# IRQF401RCT6.net
KiCad netlist of a schematic drawn in EAGLE
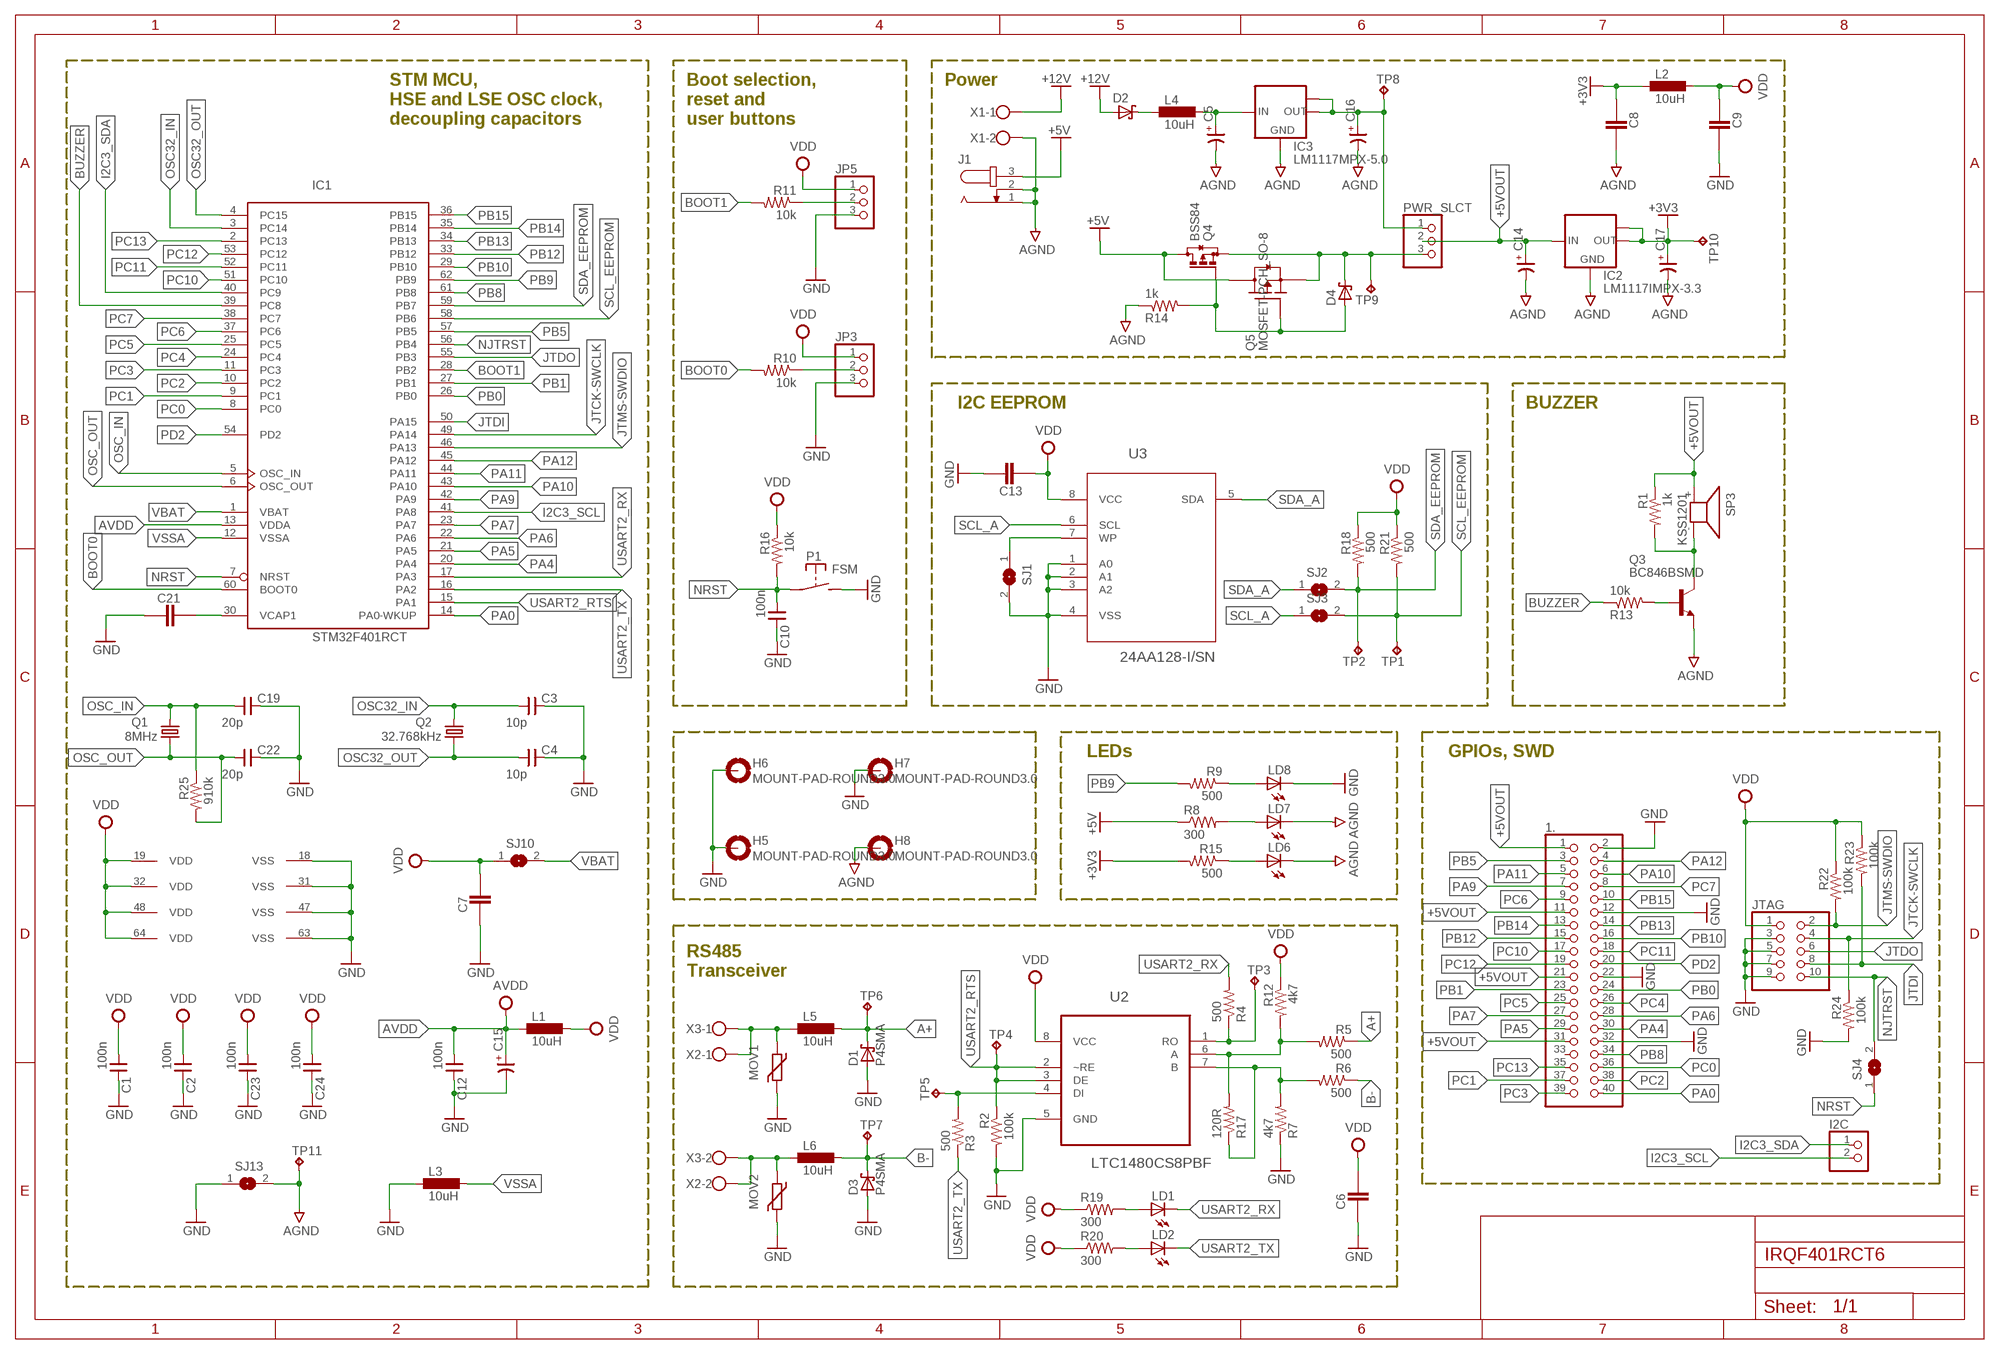
[diagram p0: schematic, sheet 1]

(export (version "E")
  (design (tool "Eeschema 10.0.6"))
  (components
    (comp (ref "1.")
      (value "PINHD-2X20")
      (footprint "eagle-import:2X20")
      (libsource (lib "eagle-import") (part "PINHD-2X20"))
    )
    (comp (ref "C1")
      (value "100n")
      (footprint "eagle-import:0805")
      (libsource (lib "eagle-import") (part "CNP-0805"))
    )
    (comp (ref "C2")
      (value "100n")
      (footprint "eagle-import:0805")
      (libsource (lib "eagle-import") (part "CNP-0805"))
    )
    (comp (ref "C3")
      (value "10p")
      (footprint "eagle-import:0805")
      (libsource (lib "eagle-import") (part "CNP-0805"))
    )
    (comp (ref "C4")
      (value "10p")
      (footprint "eagle-import:0805")
      (libsource (lib "eagle-import") (part "CNP-0805"))
    )
    (comp (ref "C5")
      (value "CP-3258-TE-B")
      (footprint "eagle-import:3528-TE-B")
      (libsource (lib "eagle-import") (part "CP-3258-TE-B"))
    )
    (comp (ref "C6")
      (value "CAPACITOR_1206")
      (footprint "eagle-import:CAPC3215X168N")
      (libsource (lib "eagle-import") (part "CAPACITOR_1206"))
    )
    (comp (ref "C7")
      (value "CAPACITOR_1206")
      (footprint "eagle-import:CAPC3215X168N")
      (libsource (lib "eagle-import") (part "CAPACITOR_1206"))
    )
    (comp (ref "C8")
      (value "CAPACITOR_1206")
      (footprint "eagle-import:CAPC3215X168N")
      (libsource (lib "eagle-import") (part "CAPACITOR_1206"))
    )
    (comp (ref "C9")
      (value "CAPACITOR_1206")
      (footprint "eagle-import:CAPC3215X168N")
      (libsource (lib "eagle-import") (part "CAPACITOR_1206"))
    )
    (comp (ref "C10")
      (value "100n")
      (footprint "eagle-import:0805")
      (libsource (lib "eagle-import") (part "CNP-0805"))
    )
    (comp (ref "C12")
      (value "100n")
      (footprint "eagle-import:0805")
      (libsource (lib "eagle-import") (part "CNP-0805"))
    )
    (comp (ref "C13")
      (value "CAPACITOR_1206")
      (footprint "eagle-import:CAPC3215X168N")
      (libsource (lib "eagle-import") (part "CAPACITOR_1206"))
    )
    (comp (ref "C14")
      (value "CP-3258-TE-B")
      (footprint "eagle-import:3528-TE-B")
      (libsource (lib "eagle-import") (part "CP-3258-TE-B"))
    )
    (comp (ref "C15")
      (value "CP-3216")
      (footprint "eagle-import:3216_T")
      (libsource (lib "eagle-import") (part "CP-3216"))
    )
    (comp (ref "C16")
      (value "CP-3216-TE-A")
      (footprint "eagle-import:3216-TE-A")
      (libsource (lib "eagle-import") (part "CP-3216-TE-A"))
    )
    (comp (ref "C17")
      (value "CP-3216-TE-A")
      (footprint "eagle-import:3216-TE-A")
      (libsource (lib "eagle-import") (part "CP-3216-TE-A"))
    )
    (comp (ref "C19")
      (value "20p")
      (footprint "eagle-import:0805")
      (libsource (lib "eagle-import") (part "CNP-0805"))
    )
    (comp (ref "C21")
      (value "CAPACITOR_1206")
      (footprint "eagle-import:CAPC3215X168N")
      (libsource (lib "eagle-import") (part "CAPACITOR_1206"))
    )
    (comp (ref "C22")
      (value "20p")
      (footprint "eagle-import:0805")
      (libsource (lib "eagle-import") (part "CNP-0805"))
    )
    (comp (ref "C23")
      (value "100n")
      (footprint "eagle-import:0805")
      (libsource (lib "eagle-import") (part "CNP-0805"))
    )
    (comp (ref "C24")
      (value "100n")
      (footprint "eagle-import:0805")
      (libsource (lib "eagle-import") (part "CNP-0805"))
    )
    (comp (ref "D1")
      (value "P4SMA")
      (footprint "eagle-import:SMB")
      (libsource (lib "eagle-import") (part "SCHOTTKY-DIODESMD"))
    )
    (comp (ref "D2")
      (value "SCHOTTKY_SMA")
      (footprint "eagle-import:DIOM5326X292N")
      (libsource (lib "eagle-import") (part "SCHOTTKY_SMA"))
    )
    (comp (ref "D3")
      (value "P4SMA")
      (footprint "eagle-import:SMB")
      (libsource (lib "eagle-import") (part "SCHOTTKY-DIODESMD"))
    )
    (comp (ref "D4")
      (value "SCHOTTKY_SMA")
      (footprint "eagle-import:DIOM5326X292N")
      (libsource (lib "eagle-import") (part "SCHOTTKY_SMA"))
    )
    (comp (ref "H5")
      (value "MOUNT-PAD-ROUND3.0")
      (footprint "eagle-import:3,0-PAD")
      (libsource (lib "eagle-import") (part "MOUNT-PAD-ROUND3.0"))
    )
    (comp (ref "H6")
      (value "MOUNT-PAD-ROUND3.0")
      (footprint "eagle-import:3,0-PAD")
      (libsource (lib "eagle-import") (part "MOUNT-PAD-ROUND3.0"))
    )
    (comp (ref "H7")
      (value "MOUNT-PAD-ROUND3.0")
      (footprint "eagle-import:3,0-PAD")
      (libsource (lib "eagle-import") (part "MOUNT-PAD-ROUND3.0"))
    )
    (comp (ref "H8")
      (value "MOUNT-PAD-ROUND3.0")
      (footprint "eagle-import:3,0-PAD")
      (libsource (lib "eagle-import") (part "MOUNT-PAD-ROUND3.0"))
    )
    (comp (ref "I2C")
      (value "PINHD-1X2")
      (footprint "eagle-import:1X02")
      (libsource (lib "eagle-import") (part "PINHD-1X2"))
    )
    (comp (ref "IC1")
      (value "STM32F401RCT")
      (footprint "eagle-import:LQFP64")
      (libsource (lib "eagle-import") (part "STM32F401RTC"))
    )
    (comp (ref "IC2")
      (value "LM1117IMPX-3.3")
      (footprint "eagle-import:SOT223")
      (libsource (lib "eagle-import") (part "LM1117IMPX-3.3"))
    )
    (comp (ref "IC3")
      (value "LM1117MPX-5.0")
      (footprint "eagle-import:SOT223")
      (libsource (lib "eagle-import") (part "LM1117MPX-5.0"))
    )
    (comp (ref "J1")
      (value "JACK-PLUG1")
      (footprint "eagle-import:SPC4078")
      (libsource (lib "eagle-import") (part "JACK-PLUG1"))
    )
    (comp (ref "JP3")
      (value "PINHD-1X3")
      (footprint "eagle-import:1X03")
      (libsource (lib "eagle-import") (part "PINHD-1X3"))
    )
    (comp (ref "JP5")
      (value "PINHD-1X3")
      (footprint "eagle-import:1X03")
      (libsource (lib "eagle-import") (part "PINHD-1X3"))
    )
    (comp (ref "JTAG")
      (value "PINHD-2X5")
      (footprint "eagle-import:2X05")
      (libsource (lib "eagle-import") (part "PINHD-2X5"))
    )
    (comp (ref "L1")
      (value "10uH")
      (footprint "eagle-import:INDC1608X95N")
      (libsource (lib "eagle-import") (part "INDUCTOR_0603"))
    )
    (comp (ref "L2")
      (value "10uH")
      (footprint "eagle-import:INDC1608X95N")
      (libsource (lib "eagle-import") (part "INDUCTOR_0603"))
    )
    (comp (ref "L3")
      (value "10uH")
      (footprint "eagle-import:INDC1608X95N")
      (libsource (lib "eagle-import") (part "INDUCTOR_0603"))
    )
    (comp (ref "L4")
      (value "10uH")
      (footprint "eagle-import:INDC1608X95N")
      (libsource (lib "eagle-import") (part "INDUCTOR_0603"))
    )
    (comp (ref "L5")
      (value "10uH")
      (footprint "eagle-import:INDC1608X95N")
      (libsource (lib "eagle-import") (part "INDUCTOR_0603"))
    )
    (comp (ref "L6")
      (value "10uH")
      (footprint "eagle-import:INDC1608X95N")
      (libsource (lib "eagle-import") (part "INDUCTOR_0603"))
    )
    (comp (ref "LD1")
      (value "LEDCHIPLED_0805")
      (footprint "eagle-import:CHIPLED_0805")
      (libsource (lib "eagle-import") (part "LEDCHIPLED_0805"))
    )
    (comp (ref "LD2")
      (value "LEDCHIPLED_0805")
      (footprint "eagle-import:CHIPLED_0805")
      (libsource (lib "eagle-import") (part "LEDCHIPLED_0805"))
    )
    (comp (ref "LD6")
      (value "LEDCHIPLED_0805")
      (footprint "eagle-import:CHIPLED_0805")
      (libsource (lib "eagle-import") (part "LEDCHIPLED_0805"))
    )
    (comp (ref "LD7")
      (value "LEDCHIPLED_0805")
      (footprint "eagle-import:CHIPLED_0805")
      (libsource (lib "eagle-import") (part "LEDCHIPLED_0805"))
    )
    (comp (ref "LD8")
      (value "LEDCHIPLED_0805")
      (footprint "eagle-import:CHIPLED_0805")
      (libsource (lib "eagle-import") (part "LEDCHIPLED_0805"))
    )
    (comp (ref "MOV1")
      (value "VARISTOR_0805")
      (footprint "eagle-import:VARC2012X70N")
      (libsource (lib "eagle-import") (part "VARISTOR_0805"))
    )
    (comp (ref "MOV2")
      (value "VARISTOR_0805")
      (footprint "eagle-import:VARC2012X70N")
      (libsource (lib "eagle-import") (part "VARISTOR_0805"))
    )
    (comp (ref "P1")
      (value "FSM")
      (footprint "eagle-import:FSM")
      (libsource (lib "eagle-import") (part "FSM"))
    )
    (comp (ref "PWR_SLCT")
      (value "PINHD-1X3")
      (footprint "eagle-import:1X03")
      (libsource (lib "eagle-import") (part "PINHD-1X3"))
    )
    (comp (ref "Q1")
      (value "8MHz")
      (footprint "eagle-import:HC49_S")
      (libsource (lib "eagle-import") (part "CRYTALHC49S"))
    )
    (comp (ref "Q2")
      (value "32.768kHz")
      (footprint "eagle-import:TC26H")
      (libsource (lib "eagle-import") (part "CRYTALTC26H"))
    )
    (comp (ref "Q3")
      (value "BC846BSMD")
      (footprint "eagle-import:SOT23")
      (libsource (lib "eagle-import") (part "BC846SMDB"))
    )
    (comp (ref "Q4")
      (value "BSS84")
      (footprint "eagle-import:SOT23")
      (libsource (lib "eagle-import") (part "BSS84"))
    )
    (comp (ref "Q5")
      (value "MOSFET-PCH_SO-8")
      (footprint "eagle-import:SOIC127P600X175-8AN")
      (libsource (lib "eagle-import") (part "MOSFET-PCH_SO-8"))
    )
    (comp (ref "R1")
      (value "1k")
      (footprint "eagle-import:M0805")
      (libsource (lib "eagle-import") (part "R-US_M0805"))
    )
    (comp (ref "R2")
      (value "100k")
      (footprint "eagle-import:M0805")
      (libsource (lib "eagle-import") (part "R-US_M0805"))
    )
    (comp (ref "R3")
      (value "500")
      (footprint "eagle-import:M0805")
      (libsource (lib "eagle-import") (part "R-US_M0805"))
    )
    (comp (ref "R4")
      (value "500")
      (footprint "eagle-import:M0805")
      (libsource (lib "eagle-import") (part "R-US_M0805"))
    )
    (comp (ref "R5")
      (value "500")
      (footprint "eagle-import:M0805")
      (libsource (lib "eagle-import") (part "R-US_M0805"))
    )
    (comp (ref "R6")
      (value "500")
      (footprint "eagle-import:M0805")
      (libsource (lib "eagle-import") (part "R-US_M0805"))
    )
    (comp (ref "R7")
      (value "4k7")
      (footprint "eagle-import:M0805")
      (libsource (lib "eagle-import") (part "R-US_M0805"))
    )
    (comp (ref "R8")
      (value "300")
      (footprint "eagle-import:M0805")
      (libsource (lib "eagle-import") (part "R-US_M0805"))
    )
    (comp (ref "R9")
      (value "500")
      (footprint "eagle-import:M0805")
      (libsource (lib "eagle-import") (part "R-US_M0805"))
    )
    (comp (ref "R10")
      (value "10k")
      (footprint "eagle-import:M0805")
      (libsource (lib "eagle-import") (part "R-US_M0805"))
    )
    (comp (ref "R11")
      (value "10k")
      (footprint "eagle-import:M0805")
      (libsource (lib "eagle-import") (part "R-US_M0805"))
    )
    (comp (ref "R12")
      (value "4k7")
      (footprint "eagle-import:M0805")
      (libsource (lib "eagle-import") (part "R-US_M0805"))
    )
    (comp (ref "R13")
      (value "10k")
      (footprint "eagle-import:M0805")
      (libsource (lib "eagle-import") (part "R-US_M0805"))
    )
    (comp (ref "R14")
      (value "1k")
      (footprint "eagle-import:M0805")
      (libsource (lib "eagle-import") (part "R-US_M0805"))
    )
    (comp (ref "R15")
      (value "500")
      (footprint "eagle-import:M0805")
      (libsource (lib "eagle-import") (part "R-US_M0805"))
    )
    (comp (ref "R16")
      (value "10k")
      (footprint "eagle-import:M0805")
      (libsource (lib "eagle-import") (part "R-US_M0805"))
    )
    (comp (ref "R17")
      (value "120R")
      (footprint "eagle-import:M0805")
      (libsource (lib "eagle-import") (part "R-US_M0805"))
    )
    (comp (ref "R18")
      (value "500")
      (footprint "eagle-import:M0805")
      (libsource (lib "eagle-import") (part "R-US_M0805"))
    )
    (comp (ref "R19")
      (value "300")
      (footprint "eagle-import:M0805")
      (libsource (lib "eagle-import") (part "R-US_M0805"))
    )
    (comp (ref "R20")
      (value "300")
      (footprint "eagle-import:M0805")
      (libsource (lib "eagle-import") (part "R-US_M0805"))
    )
    (comp (ref "R21")
      (value "500")
      (footprint "eagle-import:M0805")
      (libsource (lib "eagle-import") (part "R-US_M0805"))
    )
    (comp (ref "R22")
      (value "100k")
      (footprint "eagle-import:M0805")
      (libsource (lib "eagle-import") (part "R-US_M0805"))
    )
    (comp (ref "R23")
      (value "100k")
      (footprint "eagle-import:M0805")
      (libsource (lib "eagle-import") (part "R-US_M0805"))
    )
    (comp (ref "R24")
      (value "100k")
      (footprint "eagle-import:M0805")
      (libsource (lib "eagle-import") (part "R-US_M0805"))
    )
    (comp (ref "R25")
      (value "910k")
      (footprint "eagle-import:M0805")
      (libsource (lib "eagle-import") (part "R-US_M0805"))
    )
    (comp (ref "SJ1") (value "SJ") (footprint "eagle-import:SJ") (libsource (lib "eagle-import") (part "SJ")))
    (comp (ref "SJ2") (value "SJ") (footprint "eagle-import:SJ") (libsource (lib "eagle-import") (part "SJ")))
    (comp (ref "SJ3") (value "SJ") (footprint "eagle-import:SJ") (libsource (lib "eagle-import") (part "SJ")))
    (comp (ref "SJ4") (value "SJ") (footprint "eagle-import:SJ") (libsource (lib "eagle-import") (part "SJ")))
    (comp (ref "SJ10")
      (value "SJ")
      (footprint "eagle-import:SJ")
      (libsource (lib "eagle-import") (part "SJ"))
    )
    (comp (ref "SJ13")
      (value "SJ")
      (footprint "eagle-import:SJ")
      (libsource (lib "eagle-import") (part "SJ"))
    )
    (comp (ref "SP3")
      (value "KSS1201")
      (footprint "eagle-import:KSS1201")
      (libsource (lib "eagle-import") (part "KSS1201"))
    )
    (comp (ref "TP1")
      (value "TPTP10R")
      (footprint "eagle-import:TP10R")
      (libsource (lib "eagle-import") (part "TPTP10R"))
    )
    (comp (ref "TP2")
      (value "TPTP10R")
      (footprint "eagle-import:TP10R")
      (libsource (lib "eagle-import") (part "TPTP10R"))
    )
    (comp (ref "TP3")
      (value "TPTP10R")
      (footprint "eagle-import:TP10R")
      (libsource (lib "eagle-import") (part "TPTP10R"))
    )
    (comp (ref "TP4")
      (value "TPTP10R")
      (footprint "eagle-import:TP10R")
      (libsource (lib "eagle-import") (part "TPTP10R"))
    )
    (comp (ref "TP5")
      (value "TPTP10R")
      (footprint "eagle-import:TP10R")
      (libsource (lib "eagle-import") (part "TPTP10R"))
    )
    (comp (ref "TP6")
      (value "TPTP10R")
      (footprint "eagle-import:TP10R")
      (libsource (lib "eagle-import") (part "TPTP10R"))
    )
    (comp (ref "TP7")
      (value "TPTP10R")
      (footprint "eagle-import:TP10R")
      (libsource (lib "eagle-import") (part "TPTP10R"))
    )
    (comp (ref "TP8")
      (value "TPTP10R")
      (footprint "eagle-import:TP10R")
      (libsource (lib "eagle-import") (part "TPTP10R"))
    )
    (comp (ref "TP9")
      (value "TPTP10R")
      (footprint "eagle-import:TP10R")
      (libsource (lib "eagle-import") (part "TPTP10R"))
    )
    (comp (ref "TP10")
      (value "TPTP10R")
      (footprint "eagle-import:TP10R")
      (libsource (lib "eagle-import") (part "TPTP10R"))
    )
    (comp (ref "TP11")
      (value "TPTP10R")
      (footprint "eagle-import:TP10R")
      (libsource (lib "eagle-import") (part "TPTP10R"))
    )
    (comp (ref "U2")
      (value "LTC1480CS8PBF")
      (footprint "eagle-import:SOIC127P600X175-8N")
      (fields (field (name "MPN") "LTC1480CS8#PBF"))
      (libsource (lib "eagle-import") (part "LTC1480CS8PBF"))
    )
    (comp (ref "U3")
      (value "24AA128-I/SN")
      (footprint "eagle-import:SOIC127P600X175-8N")
      (libsource (lib "eagle-import") (part "24AA128-I/SN"))
    )
    (comp (ref "X1")
      (value "W237-102")
      (footprint "eagle-import:W237-102")
      (libsource (lib "eagle-import") (part "W237-102"))
    )
    (comp (ref "X2")
      (value "W237-102")
      (footprint "eagle-import:W237-102")
      (libsource (lib "eagle-import") (part "W237-102"))
    )
    (comp (ref "X3")
      (value "W237-102")
      (footprint "eagle-import:W237-102")
      (libsource (lib "eagle-import") (part "W237-102"))
    )
  )
  (nets
    (net (code "1") (name "+3V3") (class "Default")
      (node (ref "C17") (pin "+") (pinfunction "+_+") (pintype "passive"))
      (node (ref "C8") (pin "1") (pinfunction "1_1") (pintype "passive"))
      (node (ref "IC2") (pin "2") (pinfunction "OUT_2") (pintype "passive"))
      (node (ref "IC2") (pin "TAB") (pinfunction "OUT1_TAB") (pintype "passive"))
      (node (ref "L2") (pin "1") (pinfunction "1_1") (pintype "passive"))
      (node (ref "R15") (pin "2") (pinfunction "2_2") (pintype "passive"))
      (node (ref "TP10") (pin "TP") (pinfunction "TP_TP") (pintype "input"))
    )
    (net (code "2") (name "+5V") (class "Default")
      (node (ref "J1") (pin "3") (pinfunction "3_3") (pintype "passive"))
      (node (ref "Q4") (pin "3") (pinfunction "D_3") (pintype "passive"))
      (node (ref "Q5") (pin "5") (pinfunction "D_5") (pintype "passive"))
      (node (ref "R8") (pin "1") (pinfunction "1_1") (pintype "passive"))
    )
    (net (code "3") (name "+5VOUT") (class "Default")
      (node (ref "1.") (pin "1") (pinfunction "1_1") (pintype "passive"))
      (node (ref "1.") (pin "11") (pinfunction "11_11") (pintype "passive"))
      (node (ref "1.") (pin "21") (pinfunction "21_21") (pintype "passive"))
      (node (ref "1.") (pin "31") (pinfunction "31_31") (pintype "passive"))
      (node (ref "C14") (pin "+") (pinfunction "+_+") (pintype "passive"))
      (node (ref "IC2") (pin "3") (pinfunction "IN_3") (pintype "input"))
      (node (ref "PWR_SLCT") (pin "2") (pinfunction "2_2") (pintype "passive"))
      (node (ref "R1") (pin "1") (pinfunction "1_1") (pintype "passive"))
      (node (ref "SP3") (pin "+") (pinfunction "1_+") (pintype "passive"))
    )
    (net (code "4") (name "+12V") (class "Default")
      (node (ref "D2") (pin "A") (pinfunction "A_A") (pintype "passive"))
      (node (ref "X1") (pin "1") (pinfunction "KL_1") (pintype "passive"))
    )
    (net (code "5") (name "A+") (class "Default")
      (node (ref "D1") (pin "C") (pinfunction "C_C") (pintype "passive"))
      (node (ref "L5") (pin "2") (pinfunction "2_2") (pintype "passive"))
      (node (ref "R5") (pin "1") (pinfunction "1_1") (pintype "passive"))
      (node (ref "TP6") (pin "TP") (pinfunction "TP_TP") (pintype "input"))
    )
    (net (code "6") (name "AGND") (class "Default")
      (node (ref "C14") (pin "-") (pinfunction "-_-") (pintype "passive"))
      (node (ref "C16") (pin "-") (pinfunction "-_-") (pintype "passive"))
      (node (ref "C17") (pin "-") (pinfunction "-_-") (pintype "passive"))
      (node (ref "C5") (pin "-") (pinfunction "-_-") (pintype "passive"))
      (node (ref "C8") (pin "2") (pinfunction "2_2") (pintype "passive"))
      (node (ref "H8") (pin "B3,0") (pinfunction "MOUNT_B3,0") (pintype "passive"))
      (node (ref "IC2") (pin "1") (pinfunction "GND_1") (pintype "input"))
      (node (ref "IC3") (pin "1") (pinfunction "GND_1") (pintype "input"))
      (node (ref "J1") (pin "1") (pinfunction "1_1") (pintype "passive"))
      (node (ref "J1") (pin "2") (pinfunction "2_2") (pintype "passive"))
      (node (ref "LD6") (pin "C") (pinfunction "C_C") (pintype "passive"))
      (node (ref "LD7") (pin "C") (pinfunction "C_C") (pintype "passive"))
      (node (ref "Q3") (pin "2") (pinfunction "E_2") (pintype "passive"))
      (node (ref "R14") (pin "1") (pinfunction "1_1") (pintype "passive"))
      (node (ref "SJ13") (pin "2") (pinfunction "2_2") (pintype "passive"))
      (node (ref "TP11") (pin "TP") (pinfunction "TP_TP") (pintype "input"))
      (node (ref "X1") (pin "2") (pinfunction "KL_2") (pintype "passive"))
    )
    (net (code "7") (name "AVDD") (class "Default")
      (node (ref "C12") (pin "1") (pinfunction "1_1") (pintype "passive"))
      (node (ref "C15") (pin "+") (pinfunction "+_+") (pintype "passive"))
      (node (ref "IC1") (pin "13") (pinfunction "VDDA_13") (pintype "power_in"))
      (node (ref "L1") (pin "1") (pinfunction "1_1") (pintype "passive"))
    )
    (net (code "8") (name "B-") (class "Default")
      (node (ref "D3") (pin "C") (pinfunction "C_C") (pintype "passive"))
      (node (ref "L6") (pin "2") (pinfunction "2_2") (pintype "passive"))
      (node (ref "R6") (pin "1") (pinfunction "1_1") (pintype "passive"))
      (node (ref "TP7") (pin "TP") (pinfunction "TP_TP") (pintype "input"))
    )
    (net (code "9") (name "BOOT0") (class "Default")
      (node (ref "IC1") (pin "60") (pinfunction "BOOT0_60") (pintype "input"))
      (node (ref "R10") (pin "2") (pinfunction "2_2") (pintype "passive"))
    )
    (net (code "10") (name "BOOT1") (class "Default")
      (node (ref "IC1") (pin "28") (pinfunction "PB2_28") (pintype "bidirectional"))
      (node (ref "R11") (pin "2") (pinfunction "2_2") (pintype "passive"))
    )
    (net (code "11") (name "BUZZER") (class "Default")
      (node (ref "IC1") (pin "39") (pinfunction "PC8_39") (pintype "bidirectional"))
      (node (ref "R13") (pin "1") (pinfunction "1_1") (pintype "passive"))
    )
    (net (code "12") (name "GND") (class "Default")
      (node (ref "1.") (pin "12") (pinfunction "12_12") (pintype "passive"))
      (node (ref "1.") (pin "2") (pinfunction "2_2") (pintype "passive"))
      (node (ref "1.") (pin "22") (pinfunction "22_22") (pintype "passive"))
      (node (ref "1.") (pin "32") (pinfunction "32_32") (pintype "passive"))
      (node (ref "C1") (pin "2") (pinfunction "2_2") (pintype "passive"))
      (node (ref "C10") (pin "2") (pinfunction "2_2") (pintype "passive"))
      (node (ref "C12") (pin "2") (pinfunction "2_2") (pintype "passive"))
      (node (ref "C13") (pin "2") (pinfunction "2_2") (pintype "passive"))
      (node (ref "C15") (pin "-") (pinfunction "-_-") (pintype "passive"))
      (node (ref "C19") (pin "2") (pinfunction "2_2") (pintype "passive"))
      (node (ref "C2") (pin "2") (pinfunction "2_2") (pintype "passive"))
      (node (ref "C21") (pin "1") (pinfunction "1_1") (pintype "passive"))
      (node (ref "C22") (pin "2") (pinfunction "2_2") (pintype "passive"))
      (node (ref "C23") (pin "2") (pinfunction "2_2") (pintype "passive"))
      (node (ref "C24") (pin "2") (pinfunction "2_2") (pintype "passive"))
      (node (ref "C3") (pin "2") (pinfunction "2_2") (pintype "passive"))
      (node (ref "C4") (pin "2") (pinfunction "2_2") (pintype "passive"))
      (node (ref "C6") (pin "1") (pinfunction "1_1") (pintype "passive"))
      (node (ref "C7") (pin "1") (pinfunction "1_1") (pintype "passive"))
      (node (ref "C9") (pin "2") (pinfunction "2_2") (pintype "passive"))
      (node (ref "D1") (pin "A") (pinfunction "A_A") (pintype "passive"))
      (node (ref "D3") (pin "A") (pinfunction "A_A") (pintype "passive"))
      (node (ref "H5") (pin "B3,0") (pinfunction "MOUNT_B3,0") (pintype "passive"))
      (node (ref "H6") (pin "B3,0") (pinfunction "MOUNT_B3,0") (pintype "passive"))
      (node (ref "H7") (pin "B3,0") (pinfunction "MOUNT_B3,0") (pintype "passive"))
      (node (ref "IC1") (pin "18") (pinfunction "VSS_18") (pintype "power_in"))
      (node (ref "IC1") (pin "31") (pinfunction "VSS_31") (pintype "power_in"))
      (node (ref "IC1") (pin "47") (pinfunction "VSS_47") (pintype "power_in"))
      (node (ref "IC1") (pin "63") (pinfunction "VSS_63") (pintype "power_in"))
      (node (ref "JP3") (pin "3") (pinfunction "3_3") (pintype "passive"))
      (node (ref "JP5") (pin "3") (pinfunction "3_3") (pintype "passive"))
      (node (ref "JTAG") (pin "3") (pinfunction "3_3") (pintype "passive"))
      (node (ref "JTAG") (pin "5") (pinfunction "5_5") (pintype "passive"))
      (node (ref "JTAG") (pin "7") (pinfunction "7_7") (pintype "passive"))
      (node (ref "JTAG") (pin "9") (pinfunction "9_9") (pintype "passive"))
      (node (ref "L3") (pin "1") (pinfunction "1_1") (pintype "passive"))
      (node (ref "LD8") (pin "C") (pinfunction "C_C") (pintype "passive"))
      (node (ref "MOV1") (pin "1") (pinfunction "1_1") (pintype "passive"))
      (node (ref "MOV2") (pin "1") (pinfunction "1_1") (pintype "passive"))
      (node (ref "P1") (pin "P$2") (pinfunction "S_P$2") (pintype "passive"))
      (node (ref "R2") (pin "2") (pinfunction "2_2") (pintype "passive"))
      (node (ref "R24") (pin "2") (pinfunction "2_2") (pintype "passive"))
      (node (ref "R7") (pin "1") (pinfunction "1_1") (pintype "passive"))
      (node (ref "SJ1") (pin "2") (pinfunction "2_2") (pintype "passive"))
      (node (ref "SJ13") (pin "1") (pinfunction "1_1") (pintype "passive"))
      (node (ref "U2") (pin "5") (pinfunction "GND_5") (pintype "passive"))
      (node (ref "U3") (pin "1") (pinfunction "A0_1") (pintype "input"))
      (node (ref "U3") (pin "2") (pinfunction "A1_2") (pintype "input"))
      (node (ref "U3") (pin "3") (pinfunction "A2_3") (pintype "input"))
      (node (ref "U3") (pin "4") (pinfunction "VSS_4") (pintype "power_in"))
    )
    (net (code "13") (name "I2C3_SCL") (class "Default")
      (node (ref "I2C") (pin "2") (pinfunction "2_2") (pintype "passive"))
      (node (ref "IC1") (pin "41") (pinfunction "PA8_41") (pintype "bidirectional"))
    )
    (net (code "14") (name "I2C3_SDA") (class "Default")
      (node (ref "I2C") (pin "1") (pinfunction "1_1") (pintype "passive"))
      (node (ref "IC1") (pin "40") (pinfunction "PC9_40") (pintype "bidirectional"))
    )
    (net (code "15") (name "JTCK-SWCLK") (class "Default")
      (node (ref "IC1") (pin "49") (pinfunction "PA14_49") (pintype "bidirectional"))
      (node (ref "JTAG") (pin "4") (pinfunction "4_4") (pintype "passive"))
      (node (ref "R24") (pin "1") (pinfunction "1_1") (pintype "passive"))
    )
    (net (code "16") (name "JTDI") (class "Default")
      (node (ref "IC1") (pin "50") (pinfunction "PA15_50") (pintype "bidirectional"))
      (node (ref "JTAG") (pin "8") (pinfunction "8_8") (pintype "passive"))
      (node (ref "R23") (pin "2") (pinfunction "2_2") (pintype "passive"))
    )
    (net (code "17") (name "JTDO") (class "Default")
      (node (ref "IC1") (pin "55") (pinfunction "PB3_55") (pintype "bidirectional"))
      (node (ref "JTAG") (pin "6") (pinfunction "6_6") (pintype "passive"))
    )
    (net (code "18") (name "JTMS-SWDIO") (class "Default")
      (node (ref "IC1") (pin "46") (pinfunction "PA13_46") (pintype "bidirectional"))
      (node (ref "JTAG") (pin "2") (pinfunction "2_2") (pintype "passive"))
      (node (ref "R22") (pin "2") (pinfunction "2_2") (pintype "passive"))
    )
    (net (code "19") (name "NJTRST") (class "Default")
      (node (ref "IC1") (pin "56") (pinfunction "PB4_56") (pintype "bidirectional"))
      (node (ref "JTAG") (pin "10") (pinfunction "10_10") (pintype "passive"))
      (node (ref "SJ4") (pin "2") (pinfunction "2_2") (pintype "passive"))
    )
    (net (code "20") (name "NRST") (class "Default")
      (node (ref "C10") (pin "1") (pinfunction "1_1") (pintype "passive"))
      (node (ref "IC1") (pin "7") (pinfunction "NRST_7") (pintype "bidirectional"))
      (node (ref "P1") (pin "P$1") (pinfunction "P_P$1") (pintype "passive"))
      (node (ref "R16") (pin "2") (pinfunction "2_2") (pintype "passive"))
      (node (ref "SJ4") (pin "1") (pinfunction "1_1") (pintype "passive"))
    )
    (net (code "21") (name "Net-(D2-PadK)") (class "Default")
      (node (ref "D2") (pin "K") (pinfunction "K_K") (pintype "passive"))
      (node (ref "L4") (pin "1") (pinfunction "1_1") (pintype "passive"))
    )
    (net (code "22") (name "Net-(IC1A-VCAP1)") (class "Default")
      (node (ref "C21") (pin "2") (pinfunction "2_2") (pintype "passive"))
      (node (ref "IC1") (pin "30") (pinfunction "VCAP1_30") (pintype "power_in"))
    )
    (net (code "23") (name "Net-(IC3-IN)") (class "Default")
      (node (ref "C5") (pin "+") (pinfunction "+_+") (pintype "passive"))
      (node (ref "IC3") (pin "3") (pinfunction "IN_3") (pintype "input"))
      (node (ref "L4") (pin "2") (pinfunction "2_2") (pintype "passive"))
    )
    (net (code "24") (name "Net-(IC3-OUT)") (class "Default")
      (node (ref "C16") (pin "+") (pinfunction "+_+") (pintype "passive"))
      (node (ref "IC3") (pin "2") (pinfunction "OUT_2") (pintype "passive"))
      (node (ref "IC3") (pin "TAB") (pinfunction "OUT1_TAB") (pintype "passive"))
      (node (ref "PWR_SLCT") (pin "1") (pinfunction "1_1") (pintype "passive"))
      (node (ref "TP8") (pin "TP") (pinfunction "TP_TP") (pintype "input"))
    )
    (net (code "25") (name "Net-(JP3-Pad2)") (class "Default")
      (node (ref "JP3") (pin "2") (pinfunction "2_2") (pintype "passive"))
      (node (ref "R10") (pin "1") (pinfunction "1_1") (pintype "passive"))
    )
    (net (code "26") (name "Net-(JP5-Pad2)") (class "Default")
      (node (ref "JP5") (pin "2") (pinfunction "2_2") (pintype "passive"))
      (node (ref "R11") (pin "1") (pinfunction "1_1") (pintype "passive"))
    )
    (net (code "27") (name "Net-(LD1-PadA)") (class "Default")
      (node (ref "LD1") (pin "A") (pinfunction "A_A") (pintype "passive"))
      (node (ref "R19") (pin "2") (pinfunction "2_2") (pintype "passive"))
    )
    (net (code "28") (name "Net-(LD2-PadA)") (class "Default")
      (node (ref "LD2") (pin "A") (pinfunction "A_A") (pintype "passive"))
      (node (ref "R20") (pin "2") (pinfunction "2_2") (pintype "passive"))
    )
    (net (code "29") (name "Net-(LD6-PadA)") (class "Default")
      (node (ref "LD6") (pin "A") (pinfunction "A_A") (pintype "passive"))
      (node (ref "R15") (pin "1") (pinfunction "1_1") (pintype "passive"))
    )
    (net (code "30") (name "Net-(LD7-PadA)") (class "Default")
      (node (ref "LD7") (pin "A") (pinfunction "A_A") (pintype "passive"))
      (node (ref "R8") (pin "2") (pinfunction "2_2") (pintype "passive"))
    )
    (net (code "31") (name "Net-(LD8-PadA)") (class "Default")
      (node (ref "LD8") (pin "A") (pinfunction "A_A") (pintype "passive"))
      (node (ref "R9") (pin "1") (pinfunction "1_1") (pintype "passive"))
    )
    (net (code "32") (name "Net-(Q3-B)") (class "Default")
      (node (ref "Q3") (pin "1") (pinfunction "B_1") (pintype "passive"))
      (node (ref "R13") (pin "2") (pinfunction "2_2") (pintype "passive"))
    )
    (net (code "33") (name "Net-(Q3-C)") (class "Default")
      (node (ref "Q3") (pin "3") (pinfunction "C_3") (pintype "passive"))
      (node (ref "R1") (pin "2") (pinfunction "2_2") (pintype "passive"))
      (node (ref "SP3") (pin "-") (pinfunction "2_-") (pintype "passive"))
    )
    (net (code "34") (name "Net-(Q4-G)") (class "Default")
      (node (ref "D4") (pin "A") (pinfunction "A_A") (pintype "passive"))
      (node (ref "Q4") (pin "1") (pinfunction "G_1") (pintype "passive"))
      (node (ref "Q5") (pin "4") (pinfunction "G_4") (pintype "passive"))
      (node (ref "R14") (pin "2") (pinfunction "2_2") (pintype "passive"))
    )
    (net (code "35") (name "Net-(Q4-S)") (class "Default")
      (node (ref "D4") (pin "K") (pinfunction "K_K") (pintype "passive"))
      (node (ref "PWR_SLCT") (pin "3") (pinfunction "3_3") (pintype "passive"))
      (node (ref "Q4") (pin "2") (pinfunction "S_2") (pintype "passive"))
      (node (ref "Q5") (pin "1") (pinfunction "S_1") (pintype "passive"))
      (node (ref "TP9") (pin "TP") (pinfunction "TP_TP") (pintype "input"))
    )
    (net (code "36") (name "Net-(U2-A)") (class "Default")
      (node (ref "R12") (pin "2") (pinfunction "2_2") (pintype "passive"))
      (node (ref "R17") (pin "2") (pinfunction "2_2") (pintype "passive"))
      (node (ref "R5") (pin "2") (pinfunction "2_2") (pintype "passive"))
      (node (ref "U2") (pin "6") (pinfunction "A_6") (pintype "bidirectional"))
    )
    (net (code "37") (name "Net-(U2-B)") (class "Default")
      (node (ref "R17") (pin "1") (pinfunction "1_1") (pintype "passive"))
      (node (ref "R6") (pin "2") (pinfunction "2_2") (pintype "passive"))
      (node (ref "R7") (pin "2") (pinfunction "2_2") (pintype "passive"))
      (node (ref "U2") (pin "7") (pinfunction "B_7") (pintype "bidirectional"))
    )
    (net (code "38") (name "Net-(U2-DI)") (class "Default")
      (node (ref "R3") (pin "2") (pinfunction "2_2") (pintype "passive"))
      (node (ref "TP5") (pin "TP") (pinfunction "TP_TP") (pintype "input"))
      (node (ref "U2") (pin "4") (pinfunction "DI_4") (pintype "input"))
    )
    (net (code "39") (name "Net-(U2-RO)") (class "Default")
      (node (ref "R4") (pin "1") (pinfunction "1_1") (pintype "passive"))
      (node (ref "TP3") (pin "TP") (pinfunction "TP_TP") (pintype "input"))
      (node (ref "U2") (pin "1") (pinfunction "RO_1") (pintype "output"))
    )
    (net (code "40") (name "Net-(U3-WP)") (class "Default")
      (node (ref "SJ1") (pin "1") (pinfunction "1_1") (pintype "passive"))
      (node (ref "U3") (pin "7") (pinfunction "WP_7") (pintype "input"))
    )
    (net (code "41") (name "Net-(X2A-KL)") (class "Default")
      (node (ref "L5") (pin "1") (pinfunction "1_1") (pintype "passive"))
      (node (ref "MOV1") (pin "2") (pinfunction "2_2") (pintype "passive"))
      (node (ref "X2") (pin "1") (pinfunction "KL_1") (pintype "passive"))
      (node (ref "X3") (pin "1") (pinfunction "KL_1") (pintype "passive"))
    )
    (net (code "42") (name "Net-(X2B-KL)") (class "Default")
      (node (ref "L6") (pin "1") (pinfunction "1_1") (pintype "passive"))
      (node (ref "MOV2") (pin "2") (pinfunction "2_2") (pintype "passive"))
      (node (ref "X2") (pin "2") (pinfunction "KL_2") (pintype "passive"))
      (node (ref "X3") (pin "2") (pinfunction "KL_2") (pintype "passive"))
    )
    (net (code "43") (name "OSC32_IN") (class "Default")
      (node (ref "C3") (pin "1") (pinfunction "1_1") (pintype "passive"))
      (node (ref "IC1") (pin "3") (pinfunction "PC14_3") (pintype "bidirectional"))
      (node (ref "Q2") (pin "2") (pinfunction "2_2") (pintype "passive"))
    )
    (net (code "44") (name "OSC32_OUT") (class "Default")
      (node (ref "C4") (pin "1") (pinfunction "1_1") (pintype "passive"))
      (node (ref "IC1") (pin "4") (pinfunction "PC15_4") (pintype "bidirectional"))
      (node (ref "Q2") (pin "1") (pinfunction "1_1") (pintype "passive"))
    )
    (net (code "45") (name "OSC_IN") (class "Default")
      (node (ref "C19") (pin "1") (pinfunction "1_1") (pintype "passive"))
      (node (ref "IC1") (pin "5") (pinfunction "OSC_IN_5") (pintype "bidirectional"))
      (node (ref "Q1") (pin "2") (pinfunction "2_2") (pintype "passive"))
      (node (ref "R25") (pin "1") (pinfunction "1_1") (pintype "passive"))
    )
    (net (code "46") (name "OSC_OUT") (class "Default")
      (node (ref "C22") (pin "1") (pinfunction "1_1") (pintype "passive"))
      (node (ref "IC1") (pin "6") (pinfunction "OSC_OUT_6") (pintype "bidirectional"))
      (node (ref "Q1") (pin "1") (pinfunction "1_1") (pintype "passive"))
      (node (ref "R25") (pin "2") (pinfunction "2_2") (pintype "passive"))
    )
    (net (code "47") (name "PA0") (class "Default")
      (node (ref "1.") (pin "40") (pinfunction "40_40") (pintype "passive"))
      (node (ref "IC1") (pin "14") (pinfunction "PA0-WKUP_14") (pintype "bidirectional"))
    )
    (net (code "48") (name "PA4") (class "Default")
      (node (ref "1.") (pin "30") (pinfunction "30_30") (pintype "passive"))
      (node (ref "IC1") (pin "20") (pinfunction "PA4_20") (pintype "bidirectional"))
    )
    (net (code "49") (name "PA5") (class "Default")
      (node (ref "1.") (pin "29") (pinfunction "29_29") (pintype "passive"))
      (node (ref "IC1") (pin "21") (pinfunction "PA5_21") (pintype "bidirectional"))
    )
    (net (code "50") (name "PA6") (class "Default")
      (node (ref "1.") (pin "28") (pinfunction "28_28") (pintype "passive"))
      (node (ref "IC1") (pin "22") (pinfunction "PA6_22") (pintype "bidirectional"))
    )
    (net (code "51") (name "PA7") (class "Default")
      (node (ref "1.") (pin "27") (pinfunction "27_27") (pintype "passive"))
      (node (ref "IC1") (pin "23") (pinfunction "PA7_23") (pintype "bidirectional"))
    )
    (net (code "52") (name "PA9") (class "Default")
      (node (ref "1.") (pin "7") (pinfunction "7_7") (pintype "passive"))
      (node (ref "IC1") (pin "42") (pinfunction "PA9_42") (pintype "bidirectional"))
    )
    (net (code "53") (name "PA10") (class "Default")
      (node (ref "1.") (pin "6") (pinfunction "6_6") (pintype "passive"))
      (node (ref "IC1") (pin "43") (pinfunction "PA10_43") (pintype "bidirectional"))
    )
    (net (code "54") (name "PA11") (class "Default")
      (node (ref "1.") (pin "5") (pinfunction "5_5") (pintype "passive"))
      (node (ref "IC1") (pin "44") (pinfunction "PA11_44") (pintype "bidirectional"))
    )
    (net (code "55") (name "PA12") (class "Default")
      (node (ref "1.") (pin "4") (pinfunction "4_4") (pintype "passive"))
      (node (ref "IC1") (pin "45") (pinfunction "PA12_45") (pintype "bidirectional"))
    )
    (net (code "56") (name "PB0") (class "Default")
      (node (ref "1.") (pin "24") (pinfunction "24_24") (pintype "passive"))
      (node (ref "IC1") (pin "26") (pinfunction "PB0_26") (pintype "bidirectional"))
    )
    (net (code "57") (name "PB1") (class "Default")
      (node (ref "1.") (pin "23") (pinfunction "23_23") (pintype "passive"))
      (node (ref "IC1") (pin "27") (pinfunction "PB1_27") (pintype "bidirectional"))
    )
    (net (code "58") (name "PB5") (class "Default")
      (node (ref "1.") (pin "3") (pinfunction "3_3") (pintype "passive"))
      (node (ref "IC1") (pin "57") (pinfunction "PB5_57") (pintype "bidirectional"))
    )
    (net (code "59") (name "PB8") (class "Default")
      (node (ref "1.") (pin "34") (pinfunction "34_34") (pintype "passive"))
      (node (ref "IC1") (pin "61") (pinfunction "PB8_61") (pintype "bidirectional"))
    )
    (net (code "60") (name "PB9") (class "Default")
      (node (ref "IC1") (pin "62") (pinfunction "PB9_62") (pintype "bidirectional"))
      (node (ref "R9") (pin "2") (pinfunction "2_2") (pintype "passive"))
    )
    (net (code "61") (name "PB10") (class "Default")
      (node (ref "1.") (pin "16") (pinfunction "16_16") (pintype "passive"))
      (node (ref "IC1") (pin "29") (pinfunction "PB10_29") (pintype "bidirectional"))
    )
    (net (code "62") (name "PB12") (class "Default")
      (node (ref "1.") (pin "15") (pinfunction "15_15") (pintype "passive"))
      (node (ref "IC1") (pin "33") (pinfunction "PB12_33") (pintype "bidirectional"))
    )
    (net (code "63") (name "PB13") (class "Default")
      (node (ref "1.") (pin "14") (pinfunction "14_14") (pintype "passive"))
      (node (ref "IC1") (pin "34") (pinfunction "PB13_34") (pintype "bidirectional"))
    )
    (net (code "64") (name "PB14") (class "Default")
      (node (ref "1.") (pin "13") (pinfunction "13_13") (pintype "passive"))
      (node (ref "IC1") (pin "35") (pinfunction "PB14_35") (pintype "bidirectional"))
    )
    (net (code "65") (name "PB15") (class "Default")
      (node (ref "1.") (pin "10") (pinfunction "10_10") (pintype "passive"))
      (node (ref "IC1") (pin "36") (pinfunction "PB15_36") (pintype "bidirectional"))
    )
    (net (code "66") (name "PC0") (class "Default")
      (node (ref "1.") (pin "36") (pinfunction "36_36") (pintype "passive"))
      (node (ref "IC1") (pin "8") (pinfunction "PC0_8") (pintype "bidirectional"))
    )
    (net (code "67") (name "PC1") (class "Default")
      (node (ref "1.") (pin "37") (pinfunction "37_37") (pintype "passive"))
      (node (ref "IC1") (pin "9") (pinfunction "PC1_9") (pintype "bidirectional"))
    )
    (net (code "68") (name "PC2") (class "Default")
      (node (ref "1.") (pin "38") (pinfunction "38_38") (pintype "passive"))
      (node (ref "IC1") (pin "10") (pinfunction "PC2_10") (pintype "bidirectional"))
    )
    (net (code "69") (name "PC3") (class "Default")
      (node (ref "1.") (pin "39") (pinfunction "39_39") (pintype "passive"))
      (node (ref "IC1") (pin "11") (pinfunction "PC3_11") (pintype "bidirectional"))
    )
    (net (code "70") (name "PC4") (class "Default")
      (node (ref "1.") (pin "26") (pinfunction "26_26") (pintype "passive"))
      (node (ref "IC1") (pin "24") (pinfunction "PC4_24") (pintype "bidirectional"))
    )
    (net (code "71") (name "PC5") (class "Default")
      (node (ref "1.") (pin "25") (pinfunction "25_25") (pintype "passive"))
      (node (ref "IC1") (pin "25") (pinfunction "PC5_25") (pintype "bidirectional"))
    )
    (net (code "72") (name "PC6") (class "Default")
      (node (ref "1.") (pin "9") (pinfunction "9_9") (pintype "passive"))
      (node (ref "IC1") (pin "37") (pinfunction "PC6_37") (pintype "bidirectional"))
    )
    (net (code "73") (name "PC7") (class "Default")
      (node (ref "1.") (pin "8") (pinfunction "8_8") (pintype "passive"))
      (node (ref "IC1") (pin "38") (pinfunction "PC7_38") (pintype "bidirectional"))
    )
    (net (code "74") (name "PC10") (class "Default")
      (node (ref "1.") (pin "17") (pinfunction "17_17") (pintype "passive"))
      (node (ref "IC1") (pin "51") (pinfunction "PC10_51") (pintype "bidirectional"))
    )
    (net (code "75") (name "PC11") (class "Default")
      (node (ref "1.") (pin "18") (pinfunction "18_18") (pintype "passive"))
      (node (ref "IC1") (pin "52") (pinfunction "PC11_52") (pintype "bidirectional"))
    )
    (net (code "76") (name "PC12") (class "Default")
      (node (ref "1.") (pin "19") (pinfunction "19_19") (pintype "passive"))
      (node (ref "IC1") (pin "53") (pinfunction "PC12_53") (pintype "bidirectional"))
    )
    (net (code "77") (name "PC13") (class "Default")
      (node (ref "1.") (pin "35") (pinfunction "35_35") (pintype "passive"))
      (node (ref "IC1") (pin "2") (pinfunction "PC13_2") (pintype "bidirectional"))
    )
    (net (code "78") (name "PD2") (class "Default")
      (node (ref "1.") (pin "20") (pinfunction "20_20") (pintype "passive"))
      (node (ref "IC1") (pin "54") (pinfunction "PD2_54") (pintype "bidirectional"))
    )
    (net (code "79") (name "SCL_A") (class "Default")
      (node (ref "SJ3") (pin "1") (pinfunction "1_1") (pintype "passive"))
      (node (ref "U3") (pin "6") (pinfunction "SCL_6") (pintype "input"))
    )
    (net (code "80") (name "SCL_EEPROM") (class "Default")
      (node (ref "IC1") (pin "58") (pinfunction "PB6_58") (pintype "bidirectional"))
      (node (ref "R21") (pin "2") (pinfunction "2_2") (pintype "passive"))
      (node (ref "SJ3") (pin "2") (pinfunction "2_2") (pintype "passive"))
      (node (ref "TP1") (pin "TP") (pinfunction "TP_TP") (pintype "input"))
    )
    (net (code "81") (name "SDA_A") (class "Default")
      (node (ref "SJ2") (pin "1") (pinfunction "1_1") (pintype "passive"))
      (node (ref "U3") (pin "5") (pinfunction "SDA_5") (pintype "bidirectional"))
    )
    (net (code "82") (name "SDA_EEPROM") (class "Default")
      (node (ref "IC1") (pin "59") (pinfunction "PB7_59") (pintype "bidirectional"))
      (node (ref "R18") (pin "2") (pinfunction "2_2") (pintype "passive"))
      (node (ref "SJ2") (pin "2") (pinfunction "2_2") (pintype "passive"))
      (node (ref "TP2") (pin "TP") (pinfunction "TP_TP") (pintype "input"))
    )
    (net (code "83") (name "USART2_RTS") (class "Default")
      (node (ref "IC1") (pin "15") (pinfunction "PA1_15") (pintype "bidirectional"))
      (node (ref "R2") (pin "1") (pinfunction "1_1") (pintype "passive"))
      (node (ref "TP4") (pin "TP") (pinfunction "TP_TP") (pintype "input"))
      (node (ref "U2") (pin "2") (pinfunction "~{RE}_2") (pintype "input"))
      (node (ref "U2") (pin "3") (pinfunction "DE_3") (pintype "input"))
    )
    (net (code "84") (name "USART2_RX") (class "Default")
      (node (ref "IC1") (pin "17") (pinfunction "PA3_17") (pintype "bidirectional"))
      (node (ref "LD1") (pin "C") (pinfunction "C_C") (pintype "passive"))
      (node (ref "R4") (pin "2") (pinfunction "2_2") (pintype "passive"))
    )
    (net (code "85") (name "USART2_TX") (class "Default")
      (node (ref "IC1") (pin "16") (pinfunction "PA2_16") (pintype "bidirectional"))
      (node (ref "LD2") (pin "C") (pinfunction "C_C") (pintype "passive"))
      (node (ref "R3") (pin "1") (pinfunction "1_1") (pintype "passive"))
    )
    (net (code "86") (name "VBAT") (class "Default")
      (node (ref "IC1") (pin "1") (pinfunction "VBAT_1") (pintype "power_in"))
      (node (ref "SJ10") (pin "2") (pinfunction "2_2") (pintype "passive"))
    )
    (net (code "87") (name "VDD") (class "Default")
      (node (ref "C1") (pin "1") (pinfunction "1_1") (pintype "passive"))
      (node (ref "C13") (pin "1") (pinfunction "1_1") (pintype "passive"))
      (node (ref "C2") (pin "1") (pinfunction "1_1") (pintype "passive"))
      (node (ref "C23") (pin "1") (pinfunction "1_1") (pintype "passive"))
      (node (ref "C24") (pin "1") (pinfunction "1_1") (pintype "passive"))
      (node (ref "C6") (pin "2") (pinfunction "2_2") (pintype "passive"))
      (node (ref "C7") (pin "2") (pinfunction "2_2") (pintype "passive"))
      (node (ref "C9") (pin "1") (pinfunction "1_1") (pintype "passive"))
      (node (ref "IC1") (pin "19") (pinfunction "VDD_19") (pintype "power_in"))
      (node (ref "IC1") (pin "32") (pinfunction "VDD_32") (pintype "power_in"))
      (node (ref "IC1") (pin "48") (pinfunction "VDD_48") (pintype "power_in"))
      (node (ref "IC1") (pin "64") (pinfunction "VDD_64") (pintype "power_in"))
      (node (ref "JP3") (pin "1") (pinfunction "1_1") (pintype "passive"))
      (node (ref "JP5") (pin "1") (pinfunction "1_1") (pintype "passive"))
      (node (ref "JTAG") (pin "1") (pinfunction "1_1") (pintype "passive"))
      (node (ref "L1") (pin "2") (pinfunction "2_2") (pintype "passive"))
      (node (ref "L2") (pin "2") (pinfunction "2_2") (pintype "passive"))
      (node (ref "R12") (pin "1") (pinfunction "1_1") (pintype "passive"))
      (node (ref "R16") (pin "1") (pinfunction "1_1") (pintype "passive"))
      (node (ref "R18") (pin "1") (pinfunction "1_1") (pintype "passive"))
      (node (ref "R19") (pin "1") (pinfunction "1_1") (pintype "passive"))
      (node (ref "R20") (pin "1") (pinfunction "1_1") (pintype "passive"))
      (node (ref "R21") (pin "1") (pinfunction "1_1") (pintype "passive"))
      (node (ref "R22") (pin "1") (pinfunction "1_1") (pintype "passive"))
      (node (ref "R23") (pin "1") (pinfunction "1_1") (pintype "passive"))
      (node (ref "SJ10") (pin "1") (pinfunction "1_1") (pintype "passive"))
      (node (ref "U2") (pin "8") (pinfunction "VCC_8") (pintype "power_in"))
      (node (ref "U3") (pin "8") (pinfunction "VCC_8") (pintype "power_in"))
    )
    (net (code "88") (name "VSSA") (class "Default")
      (node (ref "IC1") (pin "12") (pinfunction "VSSA_12") (pintype "power_in"))
      (node (ref "L3") (pin "2") (pinfunction "2_2") (pintype "passive"))
    )
    (net (code "89") (name "unconnected-(1.-Pad33)") (class "Default")
      (node (ref "1.") (pin "33") (pinfunction "33_33") (pintype "passive"))
    )
  )
)
